# PIC.net
KiCad netlist of a schematic drawn in Altium Designer
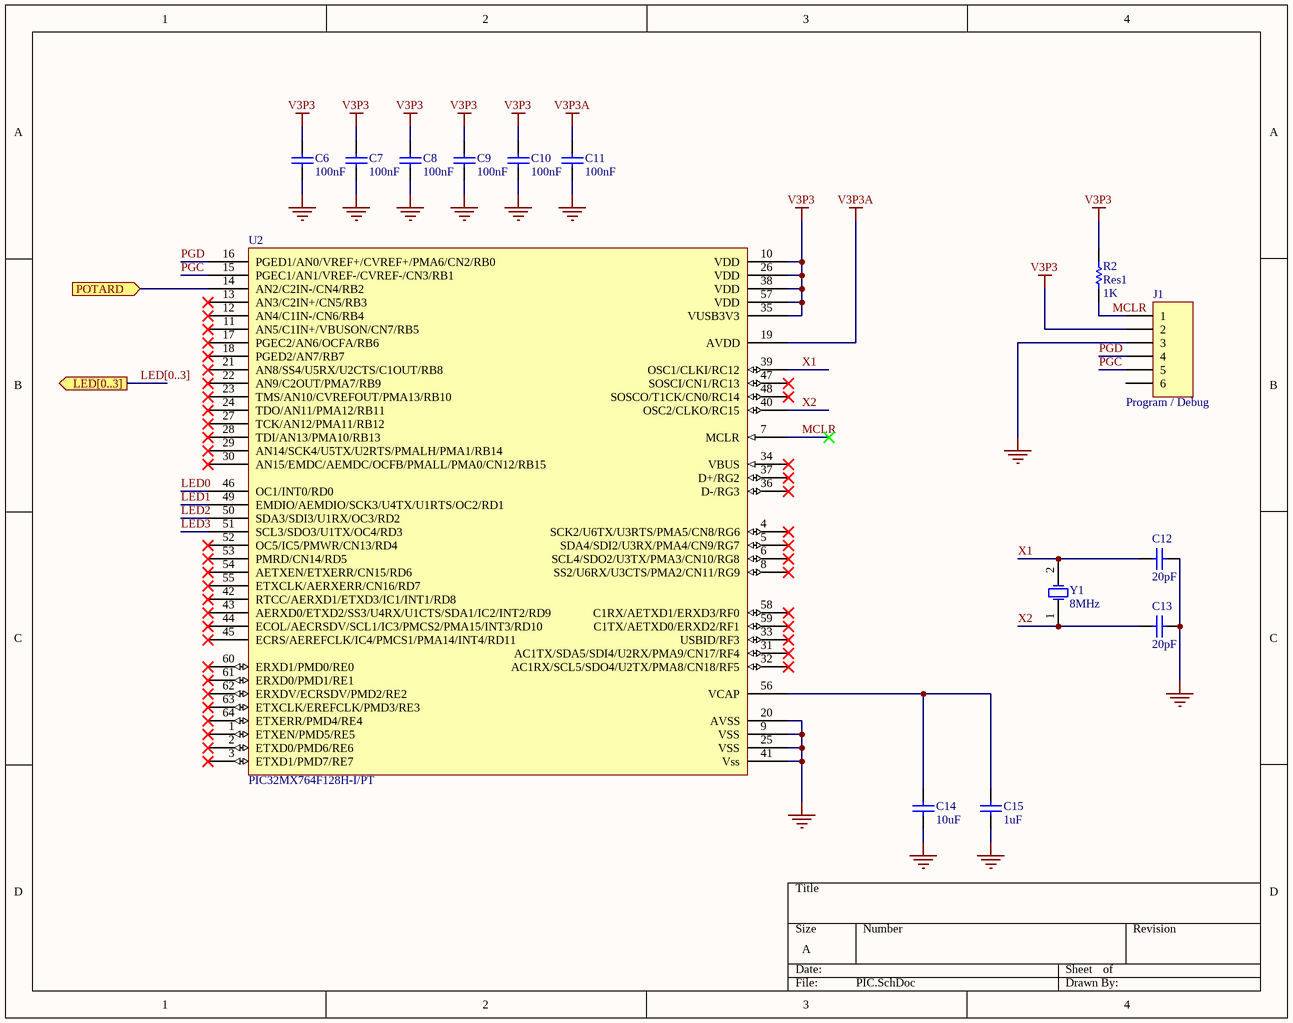
[diagram p0: PIC.SchDoc]

(export (version "E")
  (design (tool "Eeschema 10.0.6"))
  (components
    (comp (ref "C6")
      (value "100nF")
      (footprint "RAD-0.3")
      (description "Capacitor")
      (fields (field (name "PUBLISHER") "Altium Limited"))
      (libsource (lib "Miscellaneous Devices") (part "Cap"))
    )
    (comp (ref "C7")
      (value "100nF")
      (footprint "RAD-0.3")
      (description "Capacitor")
      (fields (field (name "PUBLISHER") "Altium Limited"))
      (libsource (lib "Miscellaneous Devices") (part "Cap"))
    )
    (comp (ref "C8")
      (value "100nF")
      (footprint "RAD-0.3")
      (description "Capacitor")
      (fields (field (name "PUBLISHER") "Altium Limited"))
      (libsource (lib "Miscellaneous Devices") (part "Cap"))
    )
    (comp (ref "C9")
      (value "100nF")
      (footprint "RAD-0.3")
      (description "Capacitor")
      (fields (field (name "PUBLISHER") "Altium Limited"))
      (libsource (lib "Miscellaneous Devices") (part "Cap"))
    )
    (comp (ref "C10")
      (value "100nF")
      (footprint "RAD-0.3")
      (description "Capacitor")
      (fields (field (name "PUBLISHER") "Altium Limited"))
      (libsource (lib "Miscellaneous Devices") (part "Cap"))
    )
    (comp (ref "C11")
      (value "100nF")
      (footprint "RAD-0.3")
      (description "Capacitor")
      (fields (field (name "PUBLISHER") "Altium Limited"))
      (libsource (lib "Miscellaneous Devices") (part "Cap"))
    )
    (comp (ref "C12")
      (value "20pF")
      (footprint "RAD-0.3")
      (description "Capacitor")
      (fields (field (name "PUBLISHER") "Altium Limited"))
      (libsource (lib "Miscellaneous Devices") (part "Cap"))
    )
    (comp (ref "C13")
      (value "20pF")
      (footprint "RAD-0.3")
      (description "Capacitor")
      (fields (field (name "PUBLISHER") "Altium Limited"))
      (libsource (lib "Miscellaneous Devices") (part "Cap"))
    )
    (comp (ref "C14")
      (value "10uF")
      (footprint "RAD-0.3")
      (description "Capacitor")
      (fields (field (name "PUBLISHER") "Altium Limited"))
      (libsource (lib "Miscellaneous Devices") (part "Cap"))
    )
    (comp (ref "C15")
      (value "1uF")
      (footprint "RAD-0.3")
      (description "Capacitor")
      (fields (field (name "PUBLISHER") "Altium Limited"))
      (libsource (lib "Miscellaneous Devices") (part "Cap"))
    )
    (comp (ref "J1")
      (value "Program / Debug")
      (footprint "HDR1X6")
      (description "Header, 6-Pin")
      (fields (field (name "PUBLISHER") "Altium Limited"))
      (libsource (lib "Miscellaneous Connectors") (part "Header 6"))
    )
    (comp (ref "R2")
      (value "Res1")
      (footprint "AXIAL-0.3")
      (description "Resistor")
      (fields (field (name "ALTIUM_VALUE") "1K") (field (name "PUBLISHER") "Altium Limited"))
      (libsource (lib "Miscellaneous Devices") (part "Res1"))
    )
    (comp (ref "U2") (value "PIC32MX764F128H-I/PT") (libsource (lib "tp2") (part "PIC32MX764F128H-I/PT")))
    (comp (ref "Y1")
      (value "8MHz")
      (footprint "R38")
      (description "Crystal Oscillator")
      (fields (field (name "PUBLISHER") "Altium Limited"))
      (libsource (lib "Miscellaneous Devices") (part "XTAL"))
    )
  )
  (nets
    (net (code "1") (name "/LED0") (class "Default")
      (node (ref "U2") (pin "46") (pinfunction "OC1/INT0/RD0_46") (pintype "passive"))
    )
    (net (code "2") (name "/LED1") (class "Default")
      (node (ref "U2") (pin "49") (pinfunction "EMDIO/AEMDIO/SCK3/U4TX/U1RTS/OC2/RD1_49") (pintype "passive"))
    )
    (net (code "3") (name "/LED2") (class "Default")
      (node (ref "U2") (pin "50") (pinfunction "SDA3/SDI3/U1RX/OC3/RD2_50") (pintype "passive"))
    )
    (net (code "4") (name "/LED3") (class "Default")
      (node (ref "U2") (pin "51") (pinfunction "SCL3/SDO3/U1TX/OC4/RD3_51") (pintype "passive"))
    )
    (net (code "6") (name "/MCLR") (class "Default")
      (node (ref "J1") (pin "1") (pinfunction "1_1") (pintype "passive"))
      (node (ref "R2") (pin "1") (pinfunction "1_1") (pintype "passive"))
      (node (ref "U2") (pin "7") (pinfunction "MCLR_7") (pintype "input"))
    )
    (net (code "7") (name "/PGC") (class "Default")
      (node (ref "J1") (pin "5") (pinfunction "5_5") (pintype "passive"))
      (node (ref "U2") (pin "15") (pinfunction "PGEC1/AN1/VREF-/CVREF-/CN3/RB1_15") (pintype "passive"))
    )
    (net (code "8") (name "/PGD") (class "Default")
      (node (ref "J1") (pin "4") (pinfunction "4_4") (pintype "passive"))
      (node (ref "U2") (pin "16") (pinfunction "PGED1/AN0/VREF+/CVREF+/PMA6/CN2/RB0_16") (pintype "passive"))
    )
    (net (code "9") (name "/POTARD") (class "Default")
      (node (ref "U2") (pin "14") (pinfunction "AN2/C2IN-/CN4/RB2_14") (pintype "passive"))
    )
    (net (code "10") (name "/X1") (class "Default")
      (node (ref "C12") (pin "2") (pinfunction "2_2") (pintype "passive"))
      (node (ref "U2") (pin "39") (pinfunction "OSC1/CLKI/RC12_39") (pintype "bidirectional"))
      (node (ref "Y1") (pin "2") (pinfunction "OSC2_2") (pintype "passive"))
    )
    (net (code "11") (name "/X2") (class "Default")
      (node (ref "C13") (pin "2") (pinfunction "2_2") (pintype "passive"))
      (node (ref "U2") (pin "40") (pinfunction "OSC2/CLKO/RC15_40") (pintype "bidirectional"))
      (node (ref "Y1") (pin "1") (pinfunction "OSC1_1") (pintype "passive"))
    )
    (net (code "12") (name "GND") (class "Default")
      (node (ref "C10") (pin "1") (pinfunction "1_1") (pintype "passive"))
      (node (ref "C11") (pin "1") (pinfunction "1_1") (pintype "passive"))
      (node (ref "C12") (pin "1") (pinfunction "1_1") (pintype "passive"))
      (node (ref "C13") (pin "1") (pinfunction "1_1") (pintype "passive"))
      (node (ref "C14") (pin "1") (pinfunction "1_1") (pintype "passive"))
      (node (ref "C15") (pin "1") (pinfunction "1_1") (pintype "passive"))
      (node (ref "C6") (pin "1") (pinfunction "1_1") (pintype "passive"))
      (node (ref "C7") (pin "1") (pinfunction "1_1") (pintype "passive"))
      (node (ref "C8") (pin "1") (pinfunction "1_1") (pintype "passive"))
      (node (ref "C9") (pin "1") (pinfunction "1_1") (pintype "passive"))
      (node (ref "J1") (pin "3") (pinfunction "3_3") (pintype "passive"))
      (node (ref "U2") (pin "20") (pinfunction "AVSS_20") (pintype "power_in"))
      (node (ref "U2") (pin "25") (pinfunction "VSS_25") (pintype "power_in"))
      (node (ref "U2") (pin "41") (pinfunction "Vss_41") (pintype "power_in"))
      (node (ref "U2") (pin "9") (pinfunction "VSS_9") (pintype "power_in"))
    )
    (net (code "13") (name "Net-(U2-VCAP)") (class "Default")
      (node (ref "C14") (pin "2") (pinfunction "2_2") (pintype "passive"))
      (node (ref "C15") (pin "2") (pinfunction "2_2") (pintype "passive"))
      (node (ref "U2") (pin "56") (pinfunction "VCAP_56") (pintype "power_in"))
    )
    (net (code "14") (name "V3P3") (class "Default")
      (node (ref "C10") (pin "2") (pinfunction "2_2") (pintype "passive"))
      (node (ref "C6") (pin "2") (pinfunction "2_2") (pintype "passive"))
      (node (ref "C7") (pin "2") (pinfunction "2_2") (pintype "passive"))
      (node (ref "C8") (pin "2") (pinfunction "2_2") (pintype "passive"))
      (node (ref "C9") (pin "2") (pinfunction "2_2") (pintype "passive"))
      (node (ref "J1") (pin "2") (pinfunction "2_2") (pintype "passive"))
      (node (ref "R2") (pin "2") (pinfunction "2_2") (pintype "passive"))
      (node (ref "U2") (pin "10") (pinfunction "VDD_10") (pintype "power_in"))
      (node (ref "U2") (pin "26") (pinfunction "VDD_26") (pintype "power_in"))
      (node (ref "U2") (pin "35") (pinfunction "VUSB3V3_35") (pintype "power_in"))
      (node (ref "U2") (pin "38") (pinfunction "VDD_38") (pintype "power_in"))
      (node (ref "U2") (pin "57") (pinfunction "VDD_57") (pintype "power_in"))
    )
    (net (code "15") (name "V3P3A") (class "Default")
      (node (ref "C11") (pin "2") (pinfunction "2_2") (pintype "passive"))
      (node (ref "U2") (pin "19") (pinfunction "AVDD_19") (pintype "power_in"))
    )
    (net (code "16") (name "unconnected-(J1-Pad6)") (class "Default")
      (node (ref "J1") (pin "6") (pinfunction "6_6") (pintype "passive"))
    )
    (net (code "17") (name "unconnected-(U2-AC1RX{slash}SCL5{slash}SDO4{slash}U2TX{slash}PMA8{slash}CN18{slash}RF5-Pad32)") (class "Default")
      (node (ref "U2") (pin "32") (pinfunction "AC1RX/SCL5/SDO4/U2TX/PMA8/CN18/RF5_32") (pintype "bidirectional+no_connect"))
    )
    (net (code "18") (name "unconnected-(U2-AC1TX{slash}SDA5{slash}SDI4{slash}U2RX{slash}PMA9{slash}CN17{slash}RF4-Pad31)") (class "Default")
      (node (ref "U2") (pin "31") (pinfunction "AC1TX/SDA5/SDI4/U2RX/PMA9/CN17/RF4_31") (pintype "bidirectional+no_connect"))
    )
    (net (code "19") (name "unconnected-(U2-AERXD0{slash}ETXD2{slash}SS3{slash}U4RX{slash}U1CTS{slash}SDA1{slash}IC2{slash}INT2{slash}RD9-Pad43)") (class "Default")
      (node (ref "U2") (pin "43") (pinfunction "AERXD0/ETXD2/SS3/U4RX/U1CTS/SDA1/IC2/INT2/RD9_43") (pintype "passive+no_connect"))
    )
    (net (code "20") (name "unconnected-(U2-AETXEN{slash}ETXERR{slash}CN15{slash}RD6-Pad54)") (class "Default")
      (node (ref "U2") (pin "54") (pinfunction "AETXEN/ETXERR/CN15/RD6_54") (pintype "passive+no_connect"))
    )
    (net (code "21") (name "unconnected-(U2-AN3{slash}C2IN+{slash}CN5{slash}RB3-Pad13)") (class "Default")
      (node (ref "U2") (pin "13") (pinfunction "AN3/C2IN+/CN5/RB3_13") (pintype "passive+no_connect"))
    )
    (net (code "22") (name "unconnected-(U2-AN4{slash}C1IN-{slash}CN6{slash}RB4-Pad12)") (class "Default")
      (node (ref "U2") (pin "12") (pinfunction "AN4/C1IN-/CN6/RB4_12") (pintype "passive+no_connect"))
    )
    (net (code "23") (name "unconnected-(U2-AN5{slash}C1IN+{slash}VBUSON{slash}CN7{slash}RB5-Pad11)") (class "Default")
      (node (ref "U2") (pin "11") (pinfunction "AN5/C1IN+/VBUSON/CN7/RB5_11") (pintype "passive+no_connect"))
    )
    (net (code "24") (name "unconnected-(U2-AN8{slash}SS4{slash}U5RX{slash}U2CTS{slash}C1OUT{slash}RB8-Pad21)") (class "Default")
      (node (ref "U2") (pin "21") (pinfunction "AN8/SS4/U5RX/U2CTS/C1OUT/RB8_21") (pintype "passive+no_connect"))
    )
    (net (code "25") (name "unconnected-(U2-AN9{slash}C2OUT{slash}PMA7{slash}RB9-Pad22)") (class "Default")
      (node (ref "U2") (pin "22") (pinfunction "AN9/C2OUT/PMA7/RB9_22") (pintype "passive+no_connect"))
    )
    (net (code "26") (name "unconnected-(U2-AN14{slash}SCK4{slash}U5TX{slash}U2RTS{slash}PMALH{slash}PMA1{slash}RB14-Pad29)") (class "Default")
      (node (ref "U2") (pin "29") (pinfunction "AN14/SCK4/U5TX/U2RTS/PMALH/PMA1/RB14_29") (pintype "passive+no_connect"))
    )
    (net (code "27") (name "unconnected-(U2-AN15{slash}EMDC{slash}AEMDC{slash}OCFB{slash}PMALL{slash}PMA0{slash}CN12{slash}RB15-Pad30)") (class "Default")
      (node (ref "U2") (pin "30") (pinfunction "AN15/EMDC/AEMDC/OCFB/PMALL/PMA0/CN12/RB15_30") (pintype "passive+no_connect"))
    )
    (net (code "28") (name "unconnected-(U2-C1RX{slash}AETXD1{slash}ERXD3{slash}RF0-Pad58)") (class "Default")
      (node (ref "U2") (pin "58") (pinfunction "C1RX/AETXD1/ERXD3/RF0_58") (pintype "bidirectional+no_connect"))
    )
    (net (code "29") (name "unconnected-(U2-C1TX{slash}AETXD0{slash}ERXD2{slash}RF1-Pad59)") (class "Default")
      (node (ref "U2") (pin "59") (pinfunction "C1TX/AETXD0/ERXD2/RF1_59") (pintype "bidirectional+no_connect"))
    )
    (net (code "30") (name "unconnected-(U2-D+{slash}RG2-Pad37)") (class "Default")
      (node (ref "U2") (pin "37") (pinfunction "D+/RG2_37") (pintype "bidirectional+no_connect"))
    )
    (net (code "31") (name "unconnected-(U2-D-{slash}RG3-Pad36)") (class "Default")
      (node (ref "U2") (pin "36") (pinfunction "D-/RG3_36") (pintype "bidirectional+no_connect"))
    )
    (net (code "32") (name "unconnected-(U2-ECOL{slash}AECRSDV{slash}SCL1{slash}IC3{slash}PMCS2{slash}PMA15{slash}INT3{slash}RD10-Pad44)") (class "Default")
      (node (ref "U2") (pin "44") (pinfunction "ECOL/AECRSDV/SCL1/IC3/PMCS2/PMA15/INT3/RD10_44") (pintype "passive+no_connect"))
    )
    (net (code "33") (name "unconnected-(U2-ECRS{slash}AEREFCLK{slash}IC4{slash}PMCS1{slash}PMA14{slash}INT4{slash}RD11-Pad45)") (class "Default")
      (node (ref "U2") (pin "45") (pinfunction "ECRS/AEREFCLK/IC4/PMCS1/PMA14/INT4/RD11_45") (pintype "passive+no_connect"))
    )
    (net (code "34") (name "unconnected-(U2-ERXD0{slash}PMD1{slash}RE1-Pad61)") (class "Default")
      (node (ref "U2") (pin "61") (pinfunction "ERXD0/PMD1/RE1_61") (pintype "bidirectional+no_connect"))
    )
    (net (code "35") (name "unconnected-(U2-ERXD1{slash}PMD0{slash}RE0-Pad60)") (class "Default")
      (node (ref "U2") (pin "60") (pinfunction "ERXD1/PMD0/RE0_60") (pintype "bidirectional+no_connect"))
    )
    (net (code "36") (name "unconnected-(U2-ERXDV{slash}ECRSDV{slash}PMD2{slash}RE2-Pad62)") (class "Default")
      (node (ref "U2") (pin "62") (pinfunction "ERXDV/ECRSDV/PMD2/RE2_62") (pintype "bidirectional+no_connect"))
    )
    (net (code "37") (name "unconnected-(U2-ETXCLK{slash}AERXERR{slash}CN16{slash}RD7-Pad55)") (class "Default")
      (node (ref "U2") (pin "55") (pinfunction "ETXCLK/AERXERR/CN16/RD7_55") (pintype "passive+no_connect"))
    )
    (net (code "38") (name "unconnected-(U2-ETXCLK{slash}EREFCLK{slash}PMD3{slash}RE3-Pad63)") (class "Default")
      (node (ref "U2") (pin "63") (pinfunction "ETXCLK/EREFCLK/PMD3/RE3_63") (pintype "bidirectional+no_connect"))
    )
    (net (code "39") (name "unconnected-(U2-ETXD0{slash}PMD6{slash}RE6-Pad2)") (class "Default")
      (node (ref "U2") (pin "2") (pinfunction "ETXD0/PMD6/RE6_2") (pintype "bidirectional+no_connect"))
    )
    (net (code "40") (name "unconnected-(U2-ETXD1{slash}PMD7{slash}RE7-Pad3)") (class "Default")
      (node (ref "U2") (pin "3") (pinfunction "ETXD1/PMD7/RE7_3") (pintype "bidirectional+no_connect"))
    )
    (net (code "41") (name "unconnected-(U2-ETXEN{slash}PMD5{slash}RE5-Pad1)") (class "Default")
      (node (ref "U2") (pin "1") (pinfunction "ETXEN/PMD5/RE5_1") (pintype "bidirectional+no_connect"))
    )
    (net (code "42") (name "unconnected-(U2-ETXERR{slash}PMD4{slash}RE4-Pad64)") (class "Default")
      (node (ref "U2") (pin "64") (pinfunction "ETXERR/PMD4/RE4_64") (pintype "bidirectional+no_connect"))
    )
    (net (code "43") (name "unconnected-(U2-OC5{slash}IC5{slash}PMWR{slash}CN13{slash}RD4-Pad52)") (class "Default")
      (node (ref "U2") (pin "52") (pinfunction "OC5/IC5/PMWR/CN13/RD4_52") (pintype "passive+no_connect"))
    )
    (net (code "44") (name "unconnected-(U2-PGEC2{slash}AN6{slash}OCFA{slash}RB6-Pad17)") (class "Default")
      (node (ref "U2") (pin "17") (pinfunction "PGEC2/AN6/OCFA/RB6_17") (pintype "passive+no_connect"))
    )
    (net (code "45") (name "unconnected-(U2-PGED2{slash}AN7{slash}RB7-Pad18)") (class "Default")
      (node (ref "U2") (pin "18") (pinfunction "PGED2/AN7/RB7_18") (pintype "passive+no_connect"))
    )
    (net (code "46") (name "unconnected-(U2-PMRD{slash}CN14{slash}RD5-Pad53)") (class "Default")
      (node (ref "U2") (pin "53") (pinfunction "PMRD/CN14/RD5_53") (pintype "passive+no_connect"))
    )
    (net (code "47") (name "unconnected-(U2-RTCC{slash}AERXD1{slash}ETXD3{slash}IC1{slash}INT1{slash}RD8-Pad42)") (class "Default")
      (node (ref "U2") (pin "42") (pinfunction "RTCC/AERXD1/ETXD3/IC1/INT1/RD8_42") (pintype "passive+no_connect"))
    )
    (net (code "48") (name "unconnected-(U2-SCK2{slash}U6TX{slash}U3RTS{slash}PMA5{slash}CN8{slash}RG6-Pad4)") (class "Default")
      (node (ref "U2") (pin "4") (pinfunction "SCK2/U6TX/U3RTS/PMA5/CN8/RG6_4") (pintype "bidirectional+no_connect"))
    )
    (net (code "49") (name "unconnected-(U2-SCL4{slash}SDO2{slash}U3TX{slash}PMA3{slash}CN10{slash}RG8-Pad6)") (class "Default")
      (node (ref "U2") (pin "6") (pinfunction "SCL4/SDO2/U3TX/PMA3/CN10/RG8_6") (pintype "bidirectional+no_connect"))
    )
    (net (code "50") (name "unconnected-(U2-SDA4{slash}SDI2{slash}U3RX{slash}PMA4{slash}CN9{slash}RG7-Pad5)") (class "Default")
      (node (ref "U2") (pin "5") (pinfunction "SDA4/SDI2/U3RX/PMA4/CN9/RG7_5") (pintype "bidirectional+no_connect"))
    )
    (net (code "51") (name "unconnected-(U2-SOSCI{slash}CN1{slash}RC13-Pad47)") (class "Default")
      (node (ref "U2") (pin "47") (pinfunction "SOSCI/CN1/RC13_47") (pintype "bidirectional+no_connect"))
    )
    (net (code "52") (name "unconnected-(U2-SOSCO{slash}T1CK{slash}CN0{slash}RC14-Pad48)") (class "Default")
      (node (ref "U2") (pin "48") (pinfunction "SOSCO/T1CK/CN0/RC14_48") (pintype "bidirectional+no_connect"))
    )
    (net (code "53") (name "unconnected-(U2-SS2{slash}U6RX{slash}U3CTS{slash}PMA2{slash}CN11{slash}RG9-Pad8)") (class "Default")
      (node (ref "U2") (pin "8") (pinfunction "SS2/U6RX/U3CTS/PMA2/CN11/RG9_8") (pintype "bidirectional+no_connect"))
    )
    (net (code "54") (name "unconnected-(U2-TCK{slash}AN12{slash}PMA11{slash}RB12-Pad27)") (class "Default")
      (node (ref "U2") (pin "27") (pinfunction "TCK/AN12/PMA11/RB12_27") (pintype "passive+no_connect"))
    )
    (net (code "55") (name "unconnected-(U2-TDI{slash}AN13{slash}PMA10{slash}RB13-Pad28)") (class "Default")
      (node (ref "U2") (pin "28") (pinfunction "TDI/AN13/PMA10/RB13_28") (pintype "passive+no_connect"))
    )
    (net (code "56") (name "unconnected-(U2-TDO{slash}AN11{slash}PMA12{slash}RB11-Pad24)") (class "Default")
      (node (ref "U2") (pin "24") (pinfunction "TDO/AN11/PMA12/RB11_24") (pintype "passive+no_connect"))
    )
    (net (code "57") (name "unconnected-(U2-TMS{slash}AN10{slash}CVREFOUT{slash}PMA13{slash}RB10-Pad23)") (class "Default")
      (node (ref "U2") (pin "23") (pinfunction "TMS/AN10/CVREFOUT/PMA13/RB10_23") (pintype "passive+no_connect"))
    )
    (net (code "58") (name "unconnected-(U2-USBID{slash}RF3-Pad33)") (class "Default")
      (node (ref "U2") (pin "33") (pinfunction "USBID/RF3_33") (pintype "bidirectional+no_connect"))
    )
    (net (code "59") (name "unconnected-(U2-VBUS-Pad34)") (class "Default")
      (node (ref "U2") (pin "34") (pinfunction "VBUS_34") (pintype "input+no_connect"))
    )
  )
)
